# lithium-left-c.net
KiCad netlist of a schematic drawn in EAGLE
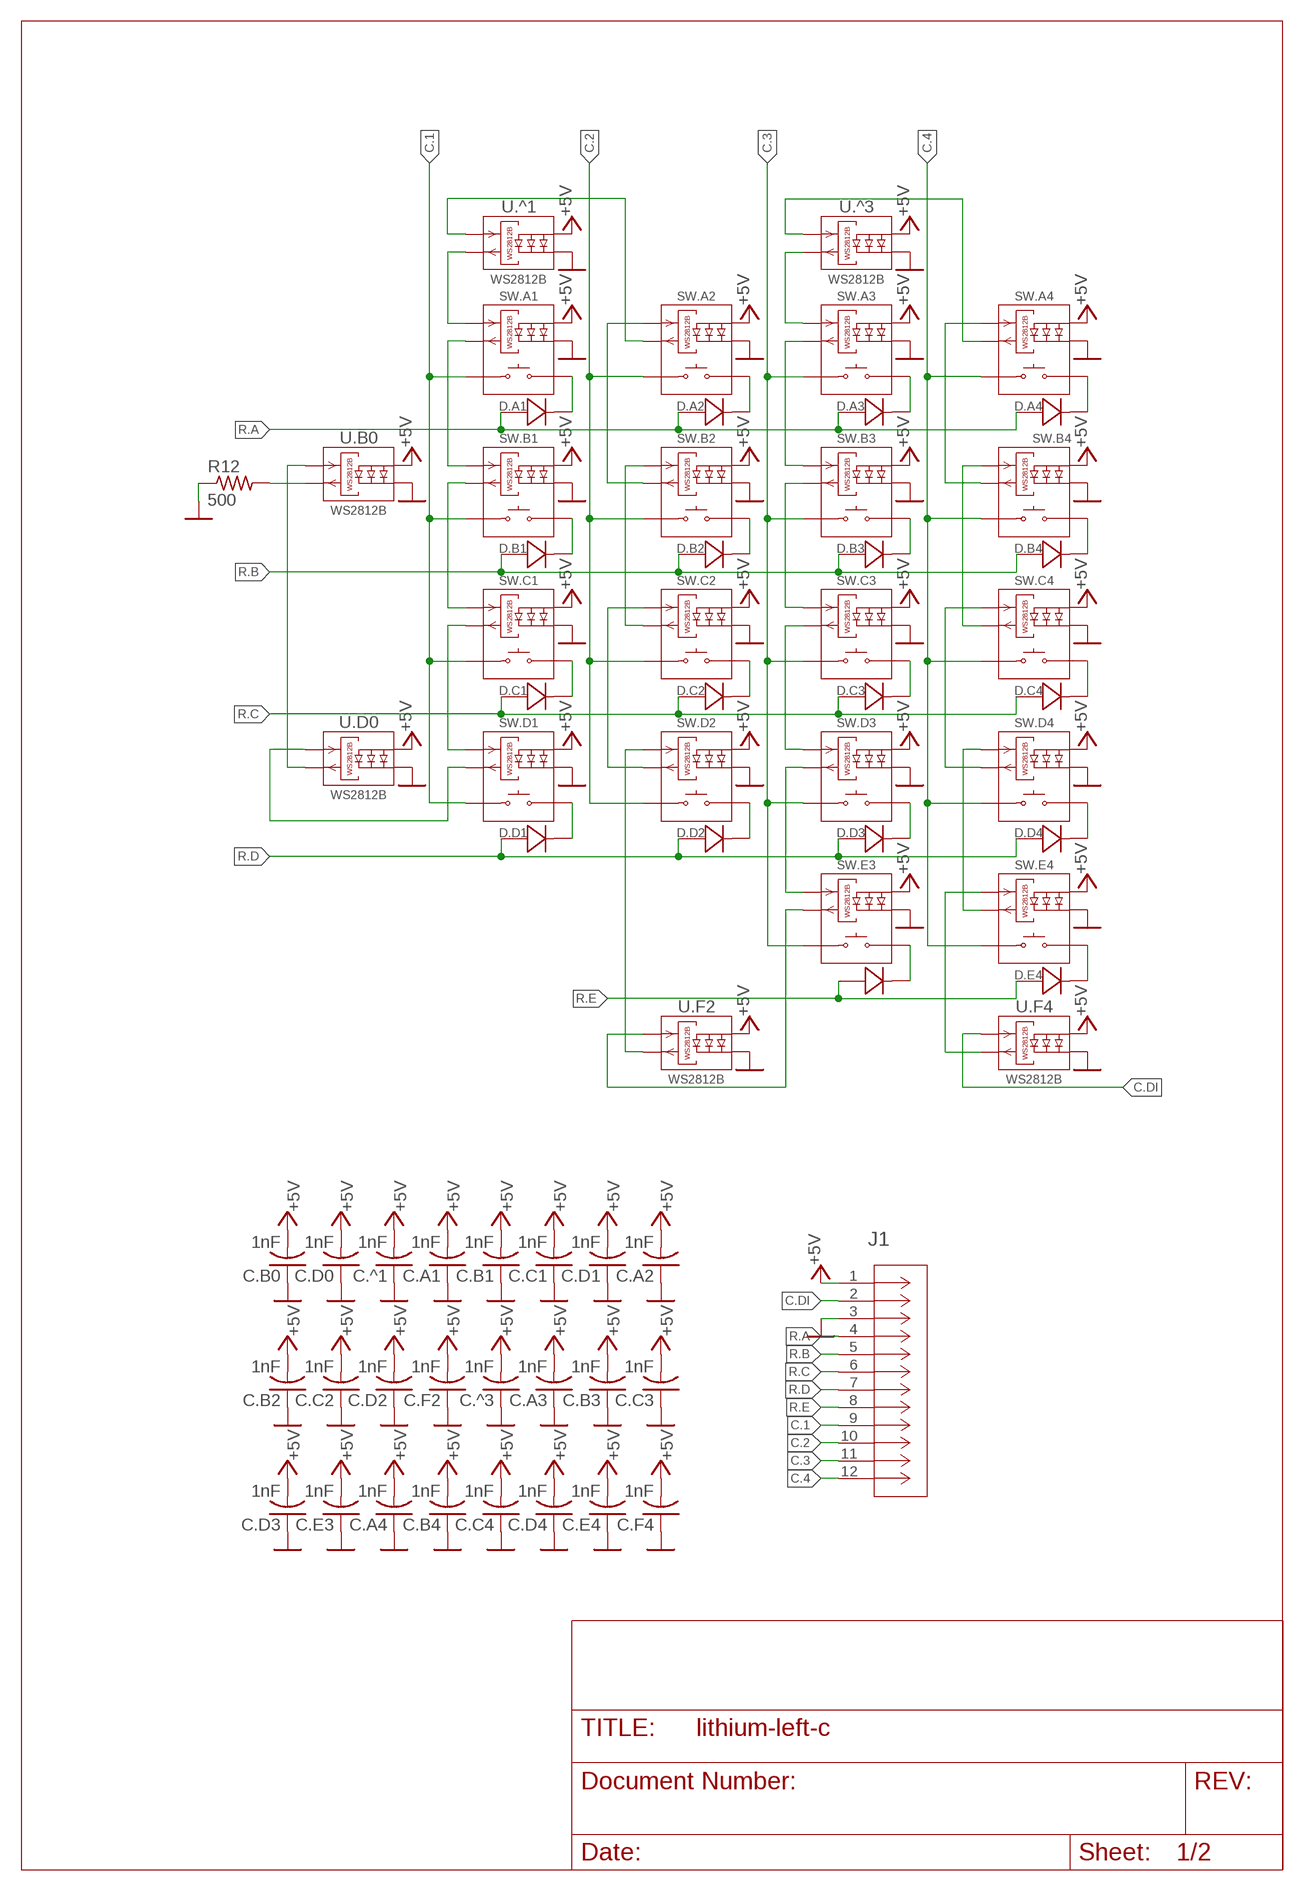
[diagram p0: schematic, sheet 1]
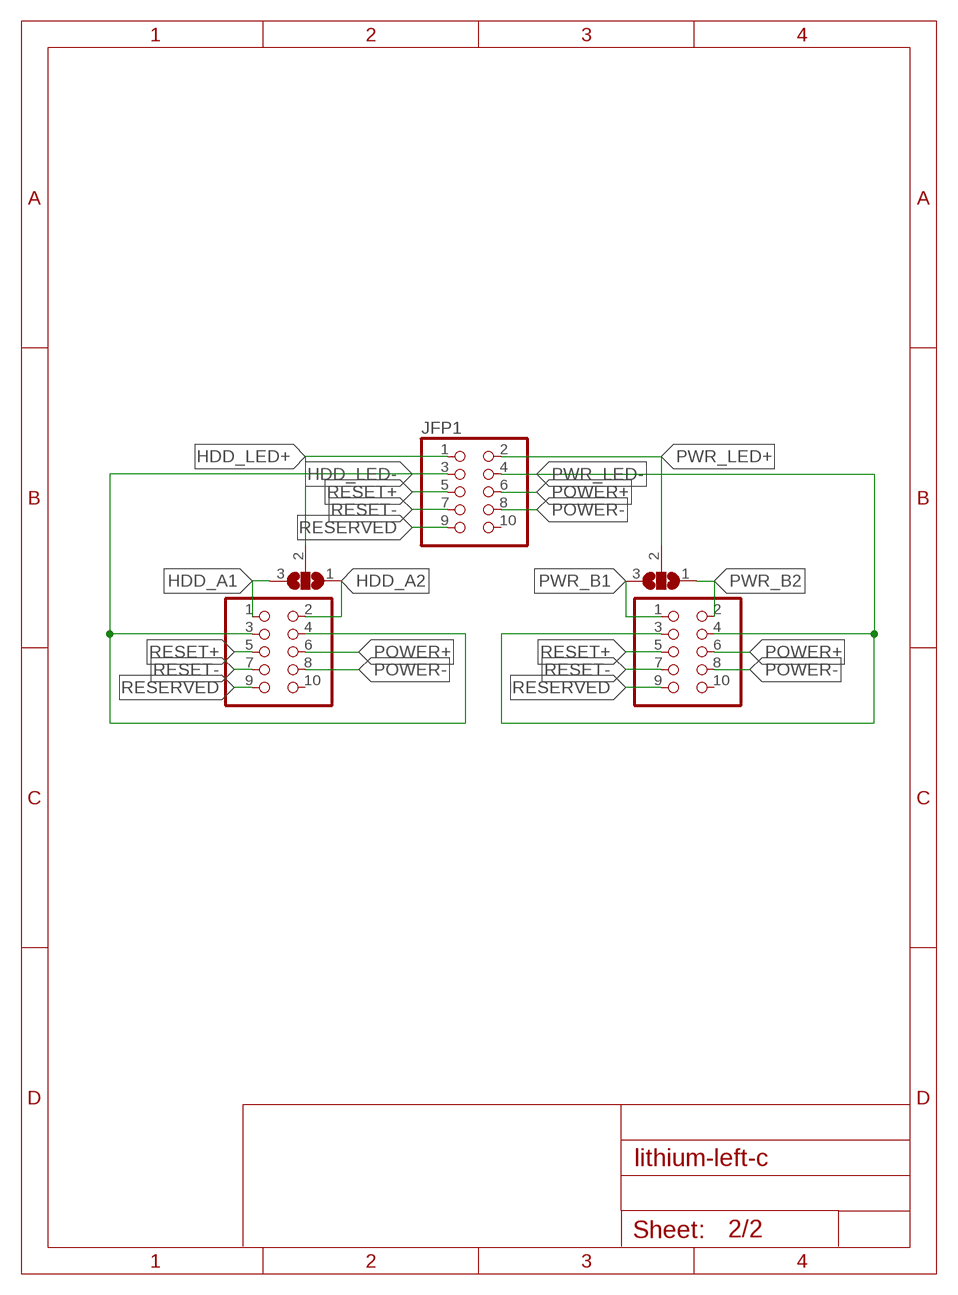
[diagram p1: schematic, sheet 2]

(export (version "E")
  (design (tool "Eeschema 10.0.6"))
  (components
    (comp (ref "HDD_LED")
      (value "PINHD-2X5")
      (footprint "eagle-import:2X05")
      (libsource (lib "eagle-import") (part "PINHD-2X5"))
    )
    (comp (ref "JFP1")
      (value "PINHD-2X5")
      (footprint "eagle-import:2X05")
      (libsource (lib "eagle-import") (part "PINHD-2X5"))
    )
    (comp (ref "J_HDD")
      (value "SJ2W")
      (footprint "eagle-import:SJ_2")
      (libsource (lib "eagle-import") (part "SJ2W"))
    )
    (comp (ref "J_PWR")
      (value "SJ2W")
      (footprint "eagle-import:SJ_2")
      (libsource (lib "eagle-import") (part "SJ2W"))
    )
    (comp (ref "PWR_LED")
      (value "PINHD-2X5")
      (footprint "eagle-import:2X05")
      (libsource (lib "eagle-import") (part "PINHD-2X5"))
    )
    (comp (ref "C.A1")
      (value "1nF")
      (footprint "eagle-import:C0805")
      (libsource (lib "eagle-import") (part "C-USC0805"))
    )
    (comp (ref "C.A2")
      (value "1nF")
      (footprint "eagle-import:C0805")
      (libsource (lib "eagle-import") (part "C-USC0805"))
    )
    (comp (ref "C.A3")
      (value "1nF")
      (footprint "eagle-import:C0805")
      (libsource (lib "eagle-import") (part "C-USC0805"))
    )
    (comp (ref "C.A4")
      (value "1nF")
      (footprint "eagle-import:C0805")
      (libsource (lib "eagle-import") (part "C-USC0805"))
    )
    (comp (ref "C.B0")
      (value "1nF")
      (footprint "eagle-import:C0805")
      (libsource (lib "eagle-import") (part "C-USC0805"))
    )
    (comp (ref "C.B1")
      (value "1nF")
      (footprint "eagle-import:C0805")
      (libsource (lib "eagle-import") (part "C-USC0805"))
    )
    (comp (ref "C.B2")
      (value "1nF")
      (footprint "eagle-import:C0805")
      (libsource (lib "eagle-import") (part "C-USC0805"))
    )
    (comp (ref "C.B3")
      (value "1nF")
      (footprint "eagle-import:C0805")
      (libsource (lib "eagle-import") (part "C-USC0805"))
    )
    (comp (ref "C.B4")
      (value "1nF")
      (footprint "eagle-import:C0805")
      (libsource (lib "eagle-import") (part "C-USC0805"))
    )
    (comp (ref "C.C1")
      (value "1nF")
      (footprint "eagle-import:C0805")
      (libsource (lib "eagle-import") (part "C-USC0805"))
    )
    (comp (ref "C.C2")
      (value "1nF")
      (footprint "eagle-import:C0805")
      (libsource (lib "eagle-import") (part "C-USC0805"))
    )
    (comp (ref "C.C3")
      (value "1nF")
      (footprint "eagle-import:C0805")
      (libsource (lib "eagle-import") (part "C-USC0805"))
    )
    (comp (ref "C.C4")
      (value "1nF")
      (footprint "eagle-import:C0805")
      (libsource (lib "eagle-import") (part "C-USC0805"))
    )
    (comp (ref "C.D0")
      (value "1nF")
      (footprint "eagle-import:C0805")
      (libsource (lib "eagle-import") (part "C-USC0805"))
    )
    (comp (ref "C.D1")
      (value "1nF")
      (footprint "eagle-import:C0805")
      (libsource (lib "eagle-import") (part "C-USC0805"))
    )
    (comp (ref "C.D2")
      (value "1nF")
      (footprint "eagle-import:C0805")
      (libsource (lib "eagle-import") (part "C-USC0805"))
    )
    (comp (ref "C.D3")
      (value "1nF")
      (footprint "eagle-import:C0805")
      (libsource (lib "eagle-import") (part "C-USC0805"))
    )
    (comp (ref "C.D4")
      (value "1nF")
      (footprint "eagle-import:C0805")
      (libsource (lib "eagle-import") (part "C-USC0805"))
    )
    (comp (ref "C.E3")
      (value "1nF")
      (footprint "eagle-import:C0805")
      (libsource (lib "eagle-import") (part "C-USC0805"))
    )
    (comp (ref "C.E4")
      (value "1nF")
      (footprint "eagle-import:C0805")
      (libsource (lib "eagle-import") (part "C-USC0805"))
    )
    (comp (ref "C.F2")
      (value "1nF")
      (footprint "eagle-import:C0805")
      (libsource (lib "eagle-import") (part "C-USC0805"))
    )
    (comp (ref "C.F4")
      (value "1nF")
      (footprint "eagle-import:C0805")
      (libsource (lib "eagle-import") (part "C-USC0805"))
    )
    (comp (ref "C.^1")
      (value "1nF")
      (footprint "eagle-import:C0805")
      (libsource (lib "eagle-import") (part "C-USC0805"))
    )
    (comp (ref "C.^3")
      (value "1nF")
      (footprint "eagle-import:C0805")
      (libsource (lib "eagle-import") (part "C-USC0805"))
    )
    (comp (ref "D.A1")
      (value "1N4148W")
      (footprint "eagle-import:CR_48W-E3-08_VIS")
      (libsource (lib "eagle-import") (part "1N4148W"))
    )
    (comp (ref "D.A2")
      (value "1N4148W")
      (footprint "eagle-import:CR_48W-E3-08_VIS")
      (libsource (lib "eagle-import") (part "1N4148W"))
    )
    (comp (ref "D.A3")
      (value "1N4148W")
      (footprint "eagle-import:CR_48W-E3-08_VIS")
      (libsource (lib "eagle-import") (part "1N4148W"))
    )
    (comp (ref "D.A4")
      (value "1N4148W")
      (footprint "eagle-import:CR_48W-E3-08_VIS")
      (libsource (lib "eagle-import") (part "1N4148W"))
    )
    (comp (ref "D.B1")
      (value "1N4148W")
      (footprint "eagle-import:CR_48W-E3-08_VIS")
      (libsource (lib "eagle-import") (part "1N4148W"))
    )
    (comp (ref "D.B2")
      (value "1N4148W")
      (footprint "eagle-import:CR_48W-E3-08_VIS")
      (libsource (lib "eagle-import") (part "1N4148W"))
    )
    (comp (ref "D.B3")
      (value "1N4148W")
      (footprint "eagle-import:CR_48W-E3-08_VIS")
      (libsource (lib "eagle-import") (part "1N4148W"))
    )
    (comp (ref "D.B4")
      (value "1N4148W")
      (footprint "eagle-import:CR_48W-E3-08_VIS")
      (libsource (lib "eagle-import") (part "1N4148W"))
    )
    (comp (ref "D.C1")
      (value "1N4148W")
      (footprint "eagle-import:CR_48W-E3-08_VIS")
      (libsource (lib "eagle-import") (part "1N4148W"))
    )
    (comp (ref "D.C2")
      (value "1N4148W")
      (footprint "eagle-import:CR_48W-E3-08_VIS")
      (libsource (lib "eagle-import") (part "1N4148W"))
    )
    (comp (ref "D.C3")
      (value "1N4148W")
      (footprint "eagle-import:CR_48W-E3-08_VIS")
      (libsource (lib "eagle-import") (part "1N4148W"))
    )
    (comp (ref "D.C4")
      (value "1N4148W")
      (footprint "eagle-import:CR_48W-E3-08_VIS")
      (libsource (lib "eagle-import") (part "1N4148W"))
    )
    (comp (ref "D.D1")
      (value "1N4148W")
      (footprint "eagle-import:CR_48W-E3-08_VIS")
      (libsource (lib "eagle-import") (part "1N4148W"))
    )
    (comp (ref "D.D2")
      (value "1N4148W")
      (footprint "eagle-import:CR_48W-E3-08_VIS")
      (libsource (lib "eagle-import") (part "1N4148W"))
    )
    (comp (ref "D.D3")
      (value "1N4148W")
      (footprint "eagle-import:CR_48W-E3-08_VIS")
      (libsource (lib "eagle-import") (part "1N4148W"))
    )
    (comp (ref "D.D4")
      (value "1N4148W")
      (footprint "eagle-import:CR_48W-E3-08_VIS")
      (libsource (lib "eagle-import") (part "1N4148W"))
    )
    (comp (ref "D.E3")
      (value "1N4148W")
      (footprint "eagle-import:CR_48W-E3-08_VIS")
      (libsource (lib "eagle-import") (part "1N4148W"))
    )
    (comp (ref "D.E4")
      (value "1N4148W")
      (footprint "eagle-import:CR_48W-E3-08_VIS")
      (libsource (lib "eagle-import") (part "1N4148W"))
    )
    (comp (ref "J1")
      (value "FFC2B28-12-G")
      (footprint "eagle-import:CONN_FFC2B28-12-G_GCT")
      (libsource (lib "eagle-import") (part "FFC2B28-12-G"))
    )
    (comp (ref "R12")
      (value "500")
      (footprint "eagle-import:R0805")
      (libsource (lib "eagle-import") (part "R-US_R0805"))
    )
    (comp (ref "SW.A1")
      (value "PG1350_LEDSD")
      (footprint "eagle-import:PG1350_SD_SK68")
      (libsource (lib "eagle-import") (part "PG1350_LEDSD"))
    )
    (comp (ref "SW.A2")
      (value "PG1350_LEDSD")
      (footprint "eagle-import:PG1350_SD_SK68")
      (libsource (lib "eagle-import") (part "PG1350_LEDSD"))
    )
    (comp (ref "SW.A3")
      (value "PG1350_LEDSD")
      (footprint "eagle-import:PG1350_SD_SK68")
      (libsource (lib "eagle-import") (part "PG1350_LEDSD"))
    )
    (comp (ref "SW.A4")
      (value "PG1350_LEDSD")
      (footprint "eagle-import:PG1350_SD_SK68")
      (libsource (lib "eagle-import") (part "PG1350_LEDSD"))
    )
    (comp (ref "SW.B1")
      (value "PG1350_LEDSD")
      (footprint "eagle-import:PG1350_SD_SK68")
      (libsource (lib "eagle-import") (part "PG1350_LEDSD"))
    )
    (comp (ref "SW.B2")
      (value "PG1350_LEDSD")
      (footprint "eagle-import:PG1350_SD_SK68")
      (libsource (lib "eagle-import") (part "PG1350_LEDSD"))
    )
    (comp (ref "SW.B3")
      (value "PG1350_LEDSD")
      (footprint "eagle-import:PG1350_SD_SK68")
      (libsource (lib "eagle-import") (part "PG1350_LEDSD"))
    )
    (comp (ref "SW.B4")
      (value "PG1350_LEDSD")
      (footprint "eagle-import:PG1350_SD_SK68")
      (libsource (lib "eagle-import") (part "PG1350_LEDSD"))
    )
    (comp (ref "SW.C1")
      (value "PG1350_LEDSD")
      (footprint "eagle-import:PG1350_SD_SK68")
      (libsource (lib "eagle-import") (part "PG1350_LEDSD"))
    )
    (comp (ref "SW.C2")
      (value "PG1350_LEDSD")
      (footprint "eagle-import:PG1350_SD_SK68")
      (libsource (lib "eagle-import") (part "PG1350_LEDSD"))
    )
    (comp (ref "SW.C3")
      (value "PG1350_LEDSD")
      (footprint "eagle-import:PG1350_SD_SK68")
      (libsource (lib "eagle-import") (part "PG1350_LEDSD"))
    )
    (comp (ref "SW.C4")
      (value "PG1350_LEDSD")
      (footprint "eagle-import:PG1350_SD_SK68")
      (libsource (lib "eagle-import") (part "PG1350_LEDSD"))
    )
    (comp (ref "SW.D1")
      (value "PG1350_LEDSD")
      (footprint "eagle-import:PG1350_SD_SK68")
      (libsource (lib "eagle-import") (part "PG1350_LEDSD"))
    )
    (comp (ref "SW.D2")
      (value "PG1350_LEDSD")
      (footprint "eagle-import:PG1350_SD_SK68")
      (libsource (lib "eagle-import") (part "PG1350_LEDSD"))
    )
    (comp (ref "SW.D3")
      (value "PG1350_LEDSD")
      (footprint "eagle-import:PG1350_SD_SK68")
      (libsource (lib "eagle-import") (part "PG1350_LEDSD"))
    )
    (comp (ref "SW.D4")
      (value "PG1350_LEDSD")
      (footprint "eagle-import:PG1350_SD_SK68")
      (libsource (lib "eagle-import") (part "PG1350_LEDSD"))
    )
    (comp (ref "SW.E3")
      (value "PG1350_LEDSD")
      (footprint "eagle-import:PG1350_SD_SK68")
      (libsource (lib "eagle-import") (part "PG1350_LEDSD"))
    )
    (comp (ref "SW.E4")
      (value "PG1350_LEDSD")
      (footprint "eagle-import:PG1350_SD_SK68")
      (libsource (lib "eagle-import") (part "PG1350_LEDSD"))
    )
    (comp (ref "U.B0")
      (value "WS2812B")
      (footprint "eagle-import:SK68-R")
      (libsource (lib "eagle-import") (part "WS2812B"))
    )
    (comp (ref "U.D0")
      (value "WS2812B")
      (footprint "eagle-import:SK68-R")
      (libsource (lib "eagle-import") (part "WS2812B"))
    )
    (comp (ref "U.F2")
      (value "WS2812B")
      (footprint "eagle-import:SK68-R")
      (libsource (lib "eagle-import") (part "WS2812B"))
    )
    (comp (ref "U.F4")
      (value "WS2812B")
      (footprint "eagle-import:SK68-R")
      (libsource (lib "eagle-import") (part "WS2812B"))
    )
    (comp (ref "U.^1")
      (value "WS2812B")
      (footprint "eagle-import:SK68-R")
      (libsource (lib "eagle-import") (part "WS2812B"))
    )
    (comp (ref "U.^3")
      (value "WS2812B")
      (footprint "eagle-import:SK68-R")
      (libsource (lib "eagle-import") (part "WS2812B"))
    )
  )
  (nets
    (net (code "1") (name "+5V") (class "Default")
      (node (ref "C.A1") (pin "2") (pinfunction "2_2") (pintype "passive"))
      (node (ref "C.A2") (pin "2") (pinfunction "2_2") (pintype "passive"))
      (node (ref "C.A3") (pin "2") (pinfunction "2_2") (pintype "passive"))
      (node (ref "C.A4") (pin "2") (pinfunction "2_2") (pintype "passive"))
      (node (ref "C.B0") (pin "2") (pinfunction "2_2") (pintype "passive"))
      (node (ref "C.B1") (pin "2") (pinfunction "2_2") (pintype "passive"))
      (node (ref "C.B2") (pin "2") (pinfunction "2_2") (pintype "passive"))
      (node (ref "C.B3") (pin "2") (pinfunction "2_2") (pintype "passive"))
      (node (ref "C.B4") (pin "2") (pinfunction "2_2") (pintype "passive"))
      (node (ref "C.C1") (pin "2") (pinfunction "2_2") (pintype "passive"))
      (node (ref "C.C2") (pin "2") (pinfunction "2_2") (pintype "passive"))
      (node (ref "C.C3") (pin "2") (pinfunction "2_2") (pintype "passive"))
      (node (ref "C.C4") (pin "2") (pinfunction "2_2") (pintype "passive"))
      (node (ref "C.D0") (pin "2") (pinfunction "2_2") (pintype "passive"))
      (node (ref "C.D1") (pin "2") (pinfunction "2_2") (pintype "passive"))
      (node (ref "C.D2") (pin "2") (pinfunction "2_2") (pintype "passive"))
      (node (ref "C.D3") (pin "2") (pinfunction "2_2") (pintype "passive"))
      (node (ref "C.D4") (pin "2") (pinfunction "2_2") (pintype "passive"))
      (node (ref "C.E3") (pin "2") (pinfunction "2_2") (pintype "passive"))
      (node (ref "C.E4") (pin "2") (pinfunction "2_2") (pintype "passive"))
      (node (ref "C.F2") (pin "2") (pinfunction "2_2") (pintype "passive"))
      (node (ref "C.F4") (pin "2") (pinfunction "2_2") (pintype "passive"))
      (node (ref "C.^1") (pin "2") (pinfunction "2_2") (pintype "passive"))
      (node (ref "C.^3") (pin "2") (pinfunction "2_2") (pintype "passive"))
      (node (ref "J1") (pin "1") (pinfunction "1_1") (pintype "passive"))
      (node (ref "SW.A1") (pin "1-VDD") (pinfunction "VDD_1-VDD") (pintype "power_in"))
      (node (ref "SW.A2") (pin "1-VDD") (pinfunction "VDD_1-VDD") (pintype "power_in"))
      (node (ref "SW.A3") (pin "1-VDD") (pinfunction "VDD_1-VDD") (pintype "power_in"))
      (node (ref "SW.A4") (pin "1-VDD") (pinfunction "VDD_1-VDD") (pintype "power_in"))
      (node (ref "SW.B1") (pin "1-VDD") (pinfunction "VDD_1-VDD") (pintype "power_in"))
      (node (ref "SW.B2") (pin "1-VDD") (pinfunction "VDD_1-VDD") (pintype "power_in"))
      (node (ref "SW.B3") (pin "1-VDD") (pinfunction "VDD_1-VDD") (pintype "power_in"))
      (node (ref "SW.B4") (pin "1-VDD") (pinfunction "VDD_1-VDD") (pintype "power_in"))
      (node (ref "SW.C1") (pin "1-VDD") (pinfunction "VDD_1-VDD") (pintype "power_in"))
      (node (ref "SW.C2") (pin "1-VDD") (pinfunction "VDD_1-VDD") (pintype "power_in"))
      (node (ref "SW.C3") (pin "1-VDD") (pinfunction "VDD_1-VDD") (pintype "power_in"))
      (node (ref "SW.C4") (pin "1-VDD") (pinfunction "VDD_1-VDD") (pintype "power_in"))
      (node (ref "SW.D1") (pin "1-VDD") (pinfunction "VDD_1-VDD") (pintype "power_in"))
      (node (ref "SW.D2") (pin "1-VDD") (pinfunction "VDD_1-VDD") (pintype "power_in"))
      (node (ref "SW.D3") (pin "1-VDD") (pinfunction "VDD_1-VDD") (pintype "power_in"))
      (node (ref "SW.D4") (pin "1-VDD") (pinfunction "VDD_1-VDD") (pintype "power_in"))
      (node (ref "SW.E3") (pin "1-VDD") (pinfunction "VDD_1-VDD") (pintype "power_in"))
      (node (ref "SW.E4") (pin "1-VDD") (pinfunction "VDD_1-VDD") (pintype "power_in"))
      (node (ref "U.B0") (pin "1-VDD") (pinfunction "VDD_1-VDD") (pintype "power_in"))
      (node (ref "U.D0") (pin "1-VDD") (pinfunction "VDD_1-VDD") (pintype "power_in"))
      (node (ref "U.F2") (pin "1-VDD") (pinfunction "VDD_1-VDD") (pintype "power_in"))
      (node (ref "U.F4") (pin "1-VDD") (pinfunction "VDD_1-VDD") (pintype "power_in"))
      (node (ref "U.^1") (pin "1-VDD") (pinfunction "VDD_1-VDD") (pintype "power_in"))
      (node (ref "U.^3") (pin "1-VDD") (pinfunction "VDD_1-VDD") (pintype "power_in"))
    )
    (net (code "2") (name "C.1") (class "Default")
      (node (ref "J1") (pin "9") (pinfunction "9_9") (pintype "passive"))
      (node (ref "SW.A1") (pin "1") (pinfunction "P$1_1") (pintype "power_in"))
      (node (ref "SW.B1") (pin "1") (pinfunction "P$1_1") (pintype "power_in"))
      (node (ref "SW.C1") (pin "1") (pinfunction "P$1_1") (pintype "power_in"))
      (node (ref "SW.D1") (pin "1") (pinfunction "P$1_1") (pintype "power_in"))
    )
    (net (code "3") (name "C.2") (class "Default")
      (node (ref "J1") (pin "10") (pinfunction "10_10") (pintype "passive"))
      (node (ref "SW.A2") (pin "1") (pinfunction "P$1_1") (pintype "power_in"))
      (node (ref "SW.B2") (pin "1") (pinfunction "P$1_1") (pintype "power_in"))
      (node (ref "SW.C2") (pin "1") (pinfunction "P$1_1") (pintype "power_in"))
      (node (ref "SW.D2") (pin "1") (pinfunction "P$1_1") (pintype "power_in"))
    )
    (net (code "4") (name "C.3") (class "Default")
      (node (ref "J1") (pin "11") (pinfunction "11_11") (pintype "passive"))
      (node (ref "SW.A3") (pin "1") (pinfunction "P$1_1") (pintype "power_in"))
      (node (ref "SW.B3") (pin "1") (pinfunction "P$1_1") (pintype "power_in"))
      (node (ref "SW.C3") (pin "1") (pinfunction "P$1_1") (pintype "power_in"))
      (node (ref "SW.D3") (pin "1") (pinfunction "P$1_1") (pintype "power_in"))
      (node (ref "SW.E3") (pin "1") (pinfunction "P$1_1") (pintype "power_in"))
    )
    (net (code "5") (name "C.4") (class "Default")
      (node (ref "J1") (pin "12") (pinfunction "12_12") (pintype "passive"))
      (node (ref "SW.A4") (pin "1") (pinfunction "P$1_1") (pintype "power_in"))
      (node (ref "SW.B4") (pin "1") (pinfunction "P$1_1") (pintype "power_in"))
      (node (ref "SW.C4") (pin "1") (pinfunction "P$1_1") (pintype "power_in"))
      (node (ref "SW.D4") (pin "1") (pinfunction "P$1_1") (pintype "power_in"))
      (node (ref "SW.E4") (pin "1") (pinfunction "P$1_1") (pintype "power_in"))
    )
    (net (code "6") (name "C.DI") (class "Default")
      (node (ref "J1") (pin "2") (pinfunction "2_2") (pintype "passive"))
      (node (ref "U.F4") (pin "4-DIN") (pinfunction "DI_4-DIN") (pintype "input"))
    )
    (net (code "7") (name "GND") (class "Default")
      (node (ref "C.A1") (pin "1") (pinfunction "1_1") (pintype "passive"))
      (node (ref "C.A2") (pin "1") (pinfunction "1_1") (pintype "passive"))
      (node (ref "C.A3") (pin "1") (pinfunction "1_1") (pintype "passive"))
      (node (ref "C.A4") (pin "1") (pinfunction "1_1") (pintype "passive"))
      (node (ref "C.B0") (pin "1") (pinfunction "1_1") (pintype "passive"))
      (node (ref "C.B1") (pin "1") (pinfunction "1_1") (pintype "passive"))
      (node (ref "C.B2") (pin "1") (pinfunction "1_1") (pintype "passive"))
      (node (ref "C.B3") (pin "1") (pinfunction "1_1") (pintype "passive"))
      (node (ref "C.B4") (pin "1") (pinfunction "1_1") (pintype "passive"))
      (node (ref "C.C1") (pin "1") (pinfunction "1_1") (pintype "passive"))
      (node (ref "C.C2") (pin "1") (pinfunction "1_1") (pintype "passive"))
      (node (ref "C.C3") (pin "1") (pinfunction "1_1") (pintype "passive"))
      (node (ref "C.C4") (pin "1") (pinfunction "1_1") (pintype "passive"))
      (node (ref "C.D0") (pin "1") (pinfunction "1_1") (pintype "passive"))
      (node (ref "C.D1") (pin "1") (pinfunction "1_1") (pintype "passive"))
      (node (ref "C.D2") (pin "1") (pinfunction "1_1") (pintype "passive"))
      (node (ref "C.D3") (pin "1") (pinfunction "1_1") (pintype "passive"))
      (node (ref "C.D4") (pin "1") (pinfunction "1_1") (pintype "passive"))
      (node (ref "C.E3") (pin "1") (pinfunction "1_1") (pintype "passive"))
      (node (ref "C.E4") (pin "1") (pinfunction "1_1") (pintype "passive"))
      (node (ref "C.F2") (pin "1") (pinfunction "1_1") (pintype "passive"))
      (node (ref "C.F4") (pin "1") (pinfunction "1_1") (pintype "passive"))
      (node (ref "C.^1") (pin "1") (pinfunction "1_1") (pintype "passive"))
      (node (ref "C.^3") (pin "1") (pinfunction "1_1") (pintype "passive"))
      (node (ref "J1") (pin "3") (pinfunction "3_3") (pintype "passive"))
      (node (ref "R12") (pin "1") (pinfunction "1_1") (pintype "passive"))
      (node (ref "SW.A1") (pin "3-GND") (pinfunction "GND_3-GND") (pintype "power_in"))
      (node (ref "SW.A2") (pin "3-GND") (pinfunction "GND_3-GND") (pintype "power_in"))
      (node (ref "SW.A3") (pin "3-GND") (pinfunction "GND_3-GND") (pintype "power_in"))
      (node (ref "SW.A4") (pin "3-GND") (pinfunction "GND_3-GND") (pintype "power_in"))
      (node (ref "SW.B1") (pin "3-GND") (pinfunction "GND_3-GND") (pintype "power_in"))
      (node (ref "SW.B2") (pin "3-GND") (pinfunction "GND_3-GND") (pintype "power_in"))
      (node (ref "SW.B3") (pin "3-GND") (pinfunction "GND_3-GND") (pintype "power_in"))
      (node (ref "SW.B4") (pin "3-GND") (pinfunction "GND_3-GND") (pintype "power_in"))
      (node (ref "SW.C1") (pin "3-GND") (pinfunction "GND_3-GND") (pintype "power_in"))
      (node (ref "SW.C2") (pin "3-GND") (pinfunction "GND_3-GND") (pintype "power_in"))
      (node (ref "SW.C3") (pin "3-GND") (pinfunction "GND_3-GND") (pintype "power_in"))
      (node (ref "SW.C4") (pin "3-GND") (pinfunction "GND_3-GND") (pintype "power_in"))
      (node (ref "SW.D1") (pin "3-GND") (pinfunction "GND_3-GND") (pintype "power_in"))
      (node (ref "SW.D2") (pin "3-GND") (pinfunction "GND_3-GND") (pintype "power_in"))
      (node (ref "SW.D3") (pin "3-GND") (pinfunction "GND_3-GND") (pintype "power_in"))
      (node (ref "SW.D4") (pin "3-GND") (pinfunction "GND_3-GND") (pintype "power_in"))
      (node (ref "SW.E3") (pin "3-GND") (pinfunction "GND_3-GND") (pintype "power_in"))
      (node (ref "SW.E4") (pin "3-GND") (pinfunction "GND_3-GND") (pintype "power_in"))
      (node (ref "U.B0") (pin "3-GND") (pinfunction "GND_3-GND") (pintype "power_in"))
      (node (ref "U.D0") (pin "3-GND") (pinfunction "GND_3-GND") (pintype "power_in"))
      (node (ref "U.F2") (pin "3-GND") (pinfunction "GND_3-GND") (pintype "power_in"))
      (node (ref "U.F4") (pin "3-GND") (pinfunction "GND_3-GND") (pintype "power_in"))
      (node (ref "U.^1") (pin "3-GND") (pinfunction "GND_3-GND") (pintype "power_in"))
      (node (ref "U.^3") (pin "3-GND") (pinfunction "GND_3-GND") (pintype "power_in"))
    )
    (net (code "8") (name "HDD_A1") (class "Default")
      (node (ref "HDD_LED") (pin "1") (pinfunction "1_1") (pintype "passive"))
      (node (ref "J_HDD") (pin "3") (pinfunction "3_3") (pintype "passive"))
    )
    (net (code "9") (name "HDD_A2") (class "Default")
      (node (ref "HDD_LED") (pin "2") (pinfunction "2_2") (pintype "passive"))
      (node (ref "J_HDD") (pin "1") (pinfunction "1_1") (pintype "passive"))
    )
    (net (code "10") (name "HDD_LED+") (class "Default")
      (node (ref "JFP1") (pin "1") (pinfunction "1_1") (pintype "passive"))
      (node (ref "J_HDD") (pin "2") (pinfunction "2_2") (pintype "passive"))
    )
    (net (code "11") (name "HDD_LED-") (class "Default")
      (node (ref "HDD_LED") (pin "3") (pinfunction "3_3") (pintype "passive"))
      (node (ref "HDD_LED") (pin "4") (pinfunction "4_4") (pintype "passive"))
      (node (ref "JFP1") (pin "3") (pinfunction "3_3") (pintype "passive"))
    )
    (net (code "12") (name "Net-(SW.A1-DI)") (class "Default")
      (node (ref "SW.A1") (pin "4-DIN") (pinfunction "DI_4-DIN") (pintype "input"))
      (node (ref "U.^1") (pin "2-DOUT") (pinfunction "DO_2-DOUT") (pintype "output"))
    )
    (net (code "13") (name "Net-(SW.A1-DO)") (class "Default")
      (node (ref "SW.A1") (pin "2-DOUT") (pinfunction "DO_2-DOUT") (pintype "output"))
      (node (ref "SW.B1") (pin "4-DIN") (pinfunction "DI_4-DIN") (pintype "input"))
    )
    (net (code "14") (name "Net-(SW.A1-P$2)") (class "Default")
      (node (ref "D.A1") (pin "1") (pinfunction "1_1") (pintype "passive"))
      (node (ref "SW.A1") (pin "2") (pinfunction "P$2_2") (pintype "power_in"))
    )
    (net (code "15") (name "Net-(SW.A2-DI)") (class "Default")
      (node (ref "SW.A2") (pin "4-DIN") (pinfunction "DI_4-DIN") (pintype "input"))
      (node (ref "SW.B2") (pin "2-DOUT") (pinfunction "DO_2-DOUT") (pintype "output"))
    )
    (net (code "16") (name "Net-(SW.A2-DO)") (class "Default")
      (node (ref "SW.A2") (pin "2-DOUT") (pinfunction "DO_2-DOUT") (pintype "output"))
      (node (ref "U.^1") (pin "4-DIN") (pinfunction "DI_4-DIN") (pintype "input"))
    )
    (net (code "17") (name "Net-(SW.A2-P$2)") (class "Default")
      (node (ref "D.A2") (pin "1") (pinfunction "1_1") (pintype "passive"))
      (node (ref "SW.A2") (pin "2") (pinfunction "P$2_2") (pintype "power_in"))
    )
    (net (code "18") (name "Net-(SW.A3-DI)") (class "Default")
      (node (ref "SW.A3") (pin "4-DIN") (pinfunction "DI_4-DIN") (pintype "input"))
      (node (ref "U.^3") (pin "2-DOUT") (pinfunction "DO_2-DOUT") (pintype "output"))
    )
    (net (code "19") (name "Net-(SW.A3-DO)") (class "Default")
      (node (ref "SW.A3") (pin "2-DOUT") (pinfunction "DO_2-DOUT") (pintype "output"))
      (node (ref "SW.B3") (pin "4-DIN") (pinfunction "DI_4-DIN") (pintype "input"))
    )
    (net (code "20") (name "Net-(SW.A3-P$2)") (class "Default")
      (node (ref "D.A3") (pin "1") (pinfunction "1_1") (pintype "passive"))
      (node (ref "SW.A3") (pin "2") (pinfunction "P$2_2") (pintype "power_in"))
    )
    (net (code "21") (name "Net-(SW.A4-DI)") (class "Default")
      (node (ref "SW.A4") (pin "4-DIN") (pinfunction "DI_4-DIN") (pintype "input"))
      (node (ref "SW.B4") (pin "2-DOUT") (pinfunction "DO_2-DOUT") (pintype "output"))
    )
    (net (code "22") (name "Net-(SW.A4-DO)") (class "Default")
      (node (ref "SW.A4") (pin "2-DOUT") (pinfunction "DO_2-DOUT") (pintype "output"))
      (node (ref "U.^3") (pin "4-DIN") (pinfunction "DI_4-DIN") (pintype "input"))
    )
    (net (code "23") (name "Net-(SW.A4-P$2)") (class "Default")
      (node (ref "D.A4") (pin "1") (pinfunction "1_1") (pintype "passive"))
      (node (ref "SW.A4") (pin "2") (pinfunction "P$2_2") (pintype "power_in"))
    )
    (net (code "24") (name "Net-(SW.B1-DO)") (class "Default")
      (node (ref "SW.B1") (pin "2-DOUT") (pinfunction "DO_2-DOUT") (pintype "output"))
      (node (ref "SW.C1") (pin "4-DIN") (pinfunction "DI_4-DIN") (pintype "input"))
    )
    (net (code "25") (name "Net-(SW.B1-P$2)") (class "Default")
      (node (ref "D.B1") (pin "1") (pinfunction "1_1") (pintype "passive"))
      (node (ref "SW.B1") (pin "2") (pinfunction "P$2_2") (pintype "power_in"))
    )
    (net (code "26") (name "Net-(SW.B2-DI)") (class "Default")
      (node (ref "SW.B2") (pin "4-DIN") (pinfunction "DI_4-DIN") (pintype "input"))
      (node (ref "SW.C2") (pin "2-DOUT") (pinfunction "DO_2-DOUT") (pintype "output"))
    )
    (net (code "27") (name "Net-(SW.B2-P$2)") (class "Default")
      (node (ref "D.B2") (pin "1") (pinfunction "1_1") (pintype "passive"))
      (node (ref "SW.B2") (pin "2") (pinfunction "P$2_2") (pintype "power_in"))
    )
    (net (code "28") (name "Net-(SW.B3-DO)") (class "Default")
      (node (ref "SW.B3") (pin "2-DOUT") (pinfunction "DO_2-DOUT") (pintype "output"))
      (node (ref "SW.C3") (pin "4-DIN") (pinfunction "DI_4-DIN") (pintype "input"))
    )
    (net (code "29") (name "Net-(SW.B3-P$2)") (class "Default")
      (node (ref "D.B3") (pin "1") (pinfunction "1_1") (pintype "passive"))
      (node (ref "SW.B3") (pin "2") (pinfunction "P$2_2") (pintype "power_in"))
    )
    (net (code "30") (name "Net-(SW.B4-DI)") (class "Default")
      (node (ref "SW.B4") (pin "4-DIN") (pinfunction "DI_4-DIN") (pintype "input"))
      (node (ref "SW.C4") (pin "2-DOUT") (pinfunction "DO_2-DOUT") (pintype "output"))
    )
    (net (code "31") (name "Net-(SW.B4-P$2)") (class "Default")
      (node (ref "D.B4") (pin "1") (pinfunction "1_1") (pintype "passive"))
      (node (ref "SW.B4") (pin "2") (pinfunction "P$2_2") (pintype "power_in"))
    )
    (net (code "32") (name "Net-(SW.C1-DO)") (class "Default")
      (node (ref "SW.C1") (pin "2-DOUT") (pinfunction "DO_2-DOUT") (pintype "output"))
      (node (ref "SW.D1") (pin "4-DIN") (pinfunction "DI_4-DIN") (pintype "input"))
    )
    (net (code "33") (name "Net-(SW.C1-P$2)") (class "Default")
      (node (ref "D.C1") (pin "1") (pinfunction "1_1") (pintype "passive"))
      (node (ref "SW.C1") (pin "2") (pinfunction "P$2_2") (pintype "power_in"))
    )
    (net (code "34") (name "Net-(SW.C2-DI)") (class "Default")
      (node (ref "SW.C2") (pin "4-DIN") (pinfunction "DI_4-DIN") (pintype "input"))
      (node (ref "SW.D2") (pin "2-DOUT") (pinfunction "DO_2-DOUT") (pintype "output"))
    )
    (net (code "35") (name "Net-(SW.C2-P$2)") (class "Default")
      (node (ref "D.C2") (pin "1") (pinfunction "1_1") (pintype "passive"))
      (node (ref "SW.C2") (pin "2") (pinfunction "P$2_2") (pintype "power_in"))
    )
    (net (code "36") (name "Net-(SW.C3-DO)") (class "Default")
      (node (ref "SW.C3") (pin "2-DOUT") (pinfunction "DO_2-DOUT") (pintype "output"))
      (node (ref "SW.D3") (pin "4-DIN") (pinfunction "DI_4-DIN") (pintype "input"))
    )
    (net (code "37") (name "Net-(SW.C3-P$2)") (class "Default")
      (node (ref "D.C3") (pin "1") (pinfunction "1_1") (pintype "passive"))
      (node (ref "SW.C3") (pin "2") (pinfunction "P$2_2") (pintype "power_in"))
    )
    (net (code "38") (name "Net-(SW.C4-DI)") (class "Default")
      (node (ref "SW.C4") (pin "4-DIN") (pinfunction "DI_4-DIN") (pintype "input"))
      (node (ref "SW.D4") (pin "2-DOUT") (pinfunction "DO_2-DOUT") (pintype "output"))
    )
    (net (code "39") (name "Net-(SW.C4-P$2)") (class "Default")
      (node (ref "D.C4") (pin "1") (pinfunction "1_1") (pintype "passive"))
      (node (ref "SW.C4") (pin "2") (pinfunction "P$2_2") (pintype "power_in"))
    )
    (net (code "40") (name "Net-(SW.D1-DO)") (class "Default")
      (node (ref "SW.D1") (pin "2-DOUT") (pinfunction "DO_2-DOUT") (pintype "output"))
      (node (ref "U.D0") (pin "4-DIN") (pinfunction "DI_4-DIN") (pintype "input"))
    )
    (net (code "41") (name "Net-(SW.D1-P$2)") (class "Default")
      (node (ref "D.D1") (pin "1") (pinfunction "1_1") (pintype "passive"))
      (node (ref "SW.D1") (pin "2") (pinfunction "P$2_2") (pintype "power_in"))
    )
    (net (code "42") (name "Net-(SW.D2-DI)") (class "Default")
      (node (ref "SW.D2") (pin "4-DIN") (pinfunction "DI_4-DIN") (pintype "input"))
      (node (ref "U.F2") (pin "2-DOUT") (pinfunction "DO_2-DOUT") (pintype "output"))
    )
    (net (code "43") (name "Net-(SW.D2-P$2)") (class "Default")
      (node (ref "D.D2") (pin "1") (pinfunction "1_1") (pintype "passive"))
      (node (ref "SW.D2") (pin "2") (pinfunction "P$2_2") (pintype "power_in"))
    )
    (net (code "44") (name "Net-(SW.D3-DO)") (class "Default")
      (node (ref "SW.D3") (pin "2-DOUT") (pinfunction "DO_2-DOUT") (pintype "output"))
      (node (ref "SW.E3") (pin "4-DIN") (pinfunction "DI_4-DIN") (pintype "input"))
    )
    (net (code "45") (name "Net-(SW.D3-P$2)") (class "Default")
      (node (ref "D.D3") (pin "1") (pinfunction "1_1") (pintype "passive"))
      (node (ref "SW.D3") (pin "2") (pinfunction "P$2_2") (pintype "power_in"))
    )
    (net (code "46") (name "Net-(SW.D4-DI)") (class "Default")
      (node (ref "SW.D4") (pin "4-DIN") (pinfunction "DI_4-DIN") (pintype "input"))
      (node (ref "SW.E4") (pin "2-DOUT") (pinfunction "DO_2-DOUT") (pintype "output"))
    )
    (net (code "47") (name "Net-(SW.D4-P$2)") (class "Default")
      (node (ref "D.D4") (pin "1") (pinfunction "1_1") (pintype "passive"))
      (node (ref "SW.D4") (pin "2") (pinfunction "P$2_2") (pintype "power_in"))
    )
    (net (code "48") (name "Net-(SW.E3-DO)") (class "Default")
      (node (ref "SW.E3") (pin "2-DOUT") (pinfunction "DO_2-DOUT") (pintype "output"))
      (node (ref "U.F2") (pin "4-DIN") (pinfunction "DI_4-DIN") (pintype "input"))
    )
    (net (code "49") (name "Net-(SW.E3-P$2)") (class "Default")
      (node (ref "D.E3") (pin "1") (pinfunction "1_1") (pintype "passive"))
      (node (ref "SW.E3") (pin "2") (pinfunction "P$2_2") (pintype "power_in"))
    )
    (net (code "50") (name "Net-(SW.E4-DI)") (class "Default")
      (node (ref "SW.E4") (pin "4-DIN") (pinfunction "DI_4-DIN") (pintype "input"))
      (node (ref "U.F4") (pin "2-DOUT") (pinfunction "DO_2-DOUT") (pintype "output"))
    )
    (net (code "51") (name "Net-(SW.E4-P$2)") (class "Default")
      (node (ref "D.E4") (pin "1") (pinfunction "1_1") (pintype "passive"))
      (node (ref "SW.E4") (pin "2") (pinfunction "P$2_2") (pintype "power_in"))
    )
    (net (code "52") (name "Net-(U.B0-DI)") (class "Default")
      (node (ref "U.B0") (pin "4-DIN") (pinfunction "DI_4-DIN") (pintype "input"))
      (node (ref "U.D0") (pin "2-DOUT") (pinfunction "DO_2-DOUT") (pintype "output"))
    )
    (net (code "53") (name "Net-(U.B0-DO)") (class "Default")
      (node (ref "R12") (pin "2") (pinfunction "2_2") (pintype "passive"))
      (node (ref "U.B0") (pin "2-DOUT") (pinfunction "DO_2-DOUT") (pintype "output"))
    )
    (net (code "54") (name "POWER+") (class "Default")
      (node (ref "HDD_LED") (pin "6") (pinfunction "6_6") (pintype "passive"))
      (node (ref "JFP1") (pin "6") (pinfunction "6_6") (pintype "passive"))
      (node (ref "PWR_LED") (pin "6") (pinfunction "6_6") (pintype "passive"))
    )
    (net (code "55") (name "POWER-") (class "Default")
      (node (ref "HDD_LED") (pin "8") (pinfunction "8_8") (pintype "passive"))
      (node (ref "JFP1") (pin "8") (pinfunction "8_8") (pintype "passive"))
      (node (ref "PWR_LED") (pin "8") (pinfunction "8_8") (pintype "passive"))
    )
    (net (code "56") (name "PWR_B1") (class "Default")
      (node (ref "J_PWR") (pin "3") (pinfunction "3_3") (pintype "passive"))
      (node (ref "PWR_LED") (pin "1") (pinfunction "1_1") (pintype "passive"))
    )
    (net (code "57") (name "PWR_B2") (class "Default")
      (node (ref "J_PWR") (pin "1") (pinfunction "1_1") (pintype "passive"))
      (node (ref "PWR_LED") (pin "2") (pinfunction "2_2") (pintype "passive"))
    )
    (net (code "58") (name "PWR_LED+") (class "Default")
      (node (ref "JFP1") (pin "2") (pinfunction "2_2") (pintype "passive"))
      (node (ref "J_PWR") (pin "2") (pinfunction "2_2") (pintype "passive"))
    )
    (net (code "59") (name "PWR_LED-") (class "Default")
      (node (ref "JFP1") (pin "4") (pinfunction "4_4") (pintype "passive"))
      (node (ref "PWR_LED") (pin "3") (pinfunction "3_3") (pintype "passive"))
      (node (ref "PWR_LED") (pin "4") (pinfunction "4_4") (pintype "passive"))
    )
    (net (code "60") (name "R.A") (class "Default")
      (node (ref "D.A1") (pin "2") (pinfunction "2_2") (pintype "passive"))
      (node (ref "D.A2") (pin "2") (pinfunction "2_2") (pintype "passive"))
      (node (ref "D.A3") (pin "2") (pinfunction "2_2") (pintype "passive"))
      (node (ref "D.A4") (pin "2") (pinfunction "2_2") (pintype "passive"))
      (node (ref "J1") (pin "4") (pinfunction "4_4") (pintype "passive"))
    )
    (net (code "61") (name "R.B") (class "Default")
      (node (ref "D.B1") (pin "2") (pinfunction "2_2") (pintype "passive"))
      (node (ref "D.B2") (pin "2") (pinfunction "2_2") (pintype "passive"))
      (node (ref "D.B3") (pin "2") (pinfunction "2_2") (pintype "passive"))
      (node (ref "D.B4") (pin "2") (pinfunction "2_2") (pintype "passive"))
      (node (ref "J1") (pin "5") (pinfunction "5_5") (pintype "passive"))
    )
    (net (code "62") (name "R.C") (class "Default")
      (node (ref "D.C1") (pin "2") (pinfunction "2_2") (pintype "passive"))
      (node (ref "D.C2") (pin "2") (pinfunction "2_2") (pintype "passive"))
      (node (ref "D.C3") (pin "2") (pinfunction "2_2") (pintype "passive"))
      (node (ref "D.C4") (pin "2") (pinfunction "2_2") (pintype "passive"))
      (node (ref "J1") (pin "6") (pinfunction "6_6") (pintype "passive"))
    )
    (net (code "63") (name "R.D") (class "Default")
      (node (ref "D.D1") (pin "2") (pinfunction "2_2") (pintype "passive"))
      (node (ref "D.D2") (pin "2") (pinfunction "2_2") (pintype "passive"))
      (node (ref "D.D3") (pin "2") (pinfunction "2_2") (pintype "passive"))
      (node (ref "D.D4") (pin "2") (pinfunction "2_2") (pintype "passive"))
      (node (ref "J1") (pin "7") (pinfunction "7_7") (pintype "passive"))
    )
    (net (code "64") (name "R.E") (class "Default")
      (node (ref "D.E3") (pin "2") (pinfunction "2_2") (pintype "passive"))
      (node (ref "D.E4") (pin "2") (pinfunction "2_2") (pintype "passive"))
      (node (ref "J1") (pin "8") (pinfunction "8_8") (pintype "passive"))
    )
    (net (code "65") (name "RESERVED") (class "Default")
      (node (ref "HDD_LED") (pin "9") (pinfunction "9_9") (pintype "passive"))
      (node (ref "JFP1") (pin "9") (pinfunction "9_9") (pintype "passive"))
      (node (ref "PWR_LED") (pin "9") (pinfunction "9_9") (pintype "passive"))
    )
    (net (code "66") (name "RESET+") (class "Default")
      (node (ref "HDD_LED") (pin "5") (pinfunction "5_5") (pintype "passive"))
      (node (ref "JFP1") (pin "5") (pinfunction "5_5") (pintype "passive"))
      (node (ref "PWR_LED") (pin "5") (pinfunction "5_5") (pintype "passive"))
    )
    (net (code "67") (name "RESET-") (class "Default")
      (node (ref "HDD_LED") (pin "7") (pinfunction "7_7") (pintype "passive"))
      (node (ref "JFP1") (pin "7") (pinfunction "7_7") (pintype "passive"))
      (node (ref "PWR_LED") (pin "7") (pinfunction "7_7") (pintype "passive"))
    )
    (net (code "68") (name "unconnected-(HDD_LED-Pad10)") (class "Default")
      (node (ref "HDD_LED") (pin "10") (pinfunction "10_10") (pintype "passive"))
    )
    (net (code "69") (name "unconnected-(JFP1-Pad10)") (class "Default")
      (node (ref "JFP1") (pin "10") (pinfunction "10_10") (pintype "passive"))
    )
    (net (code "70") (name "unconnected-(PWR_LED-Pad10)") (class "Default")
      (node (ref "PWR_LED") (pin "10") (pinfunction "10_10") (pintype "passive"))
    )
  )
)
